# Power.net
KiCad netlist of a schematic drawn in Altium Designer
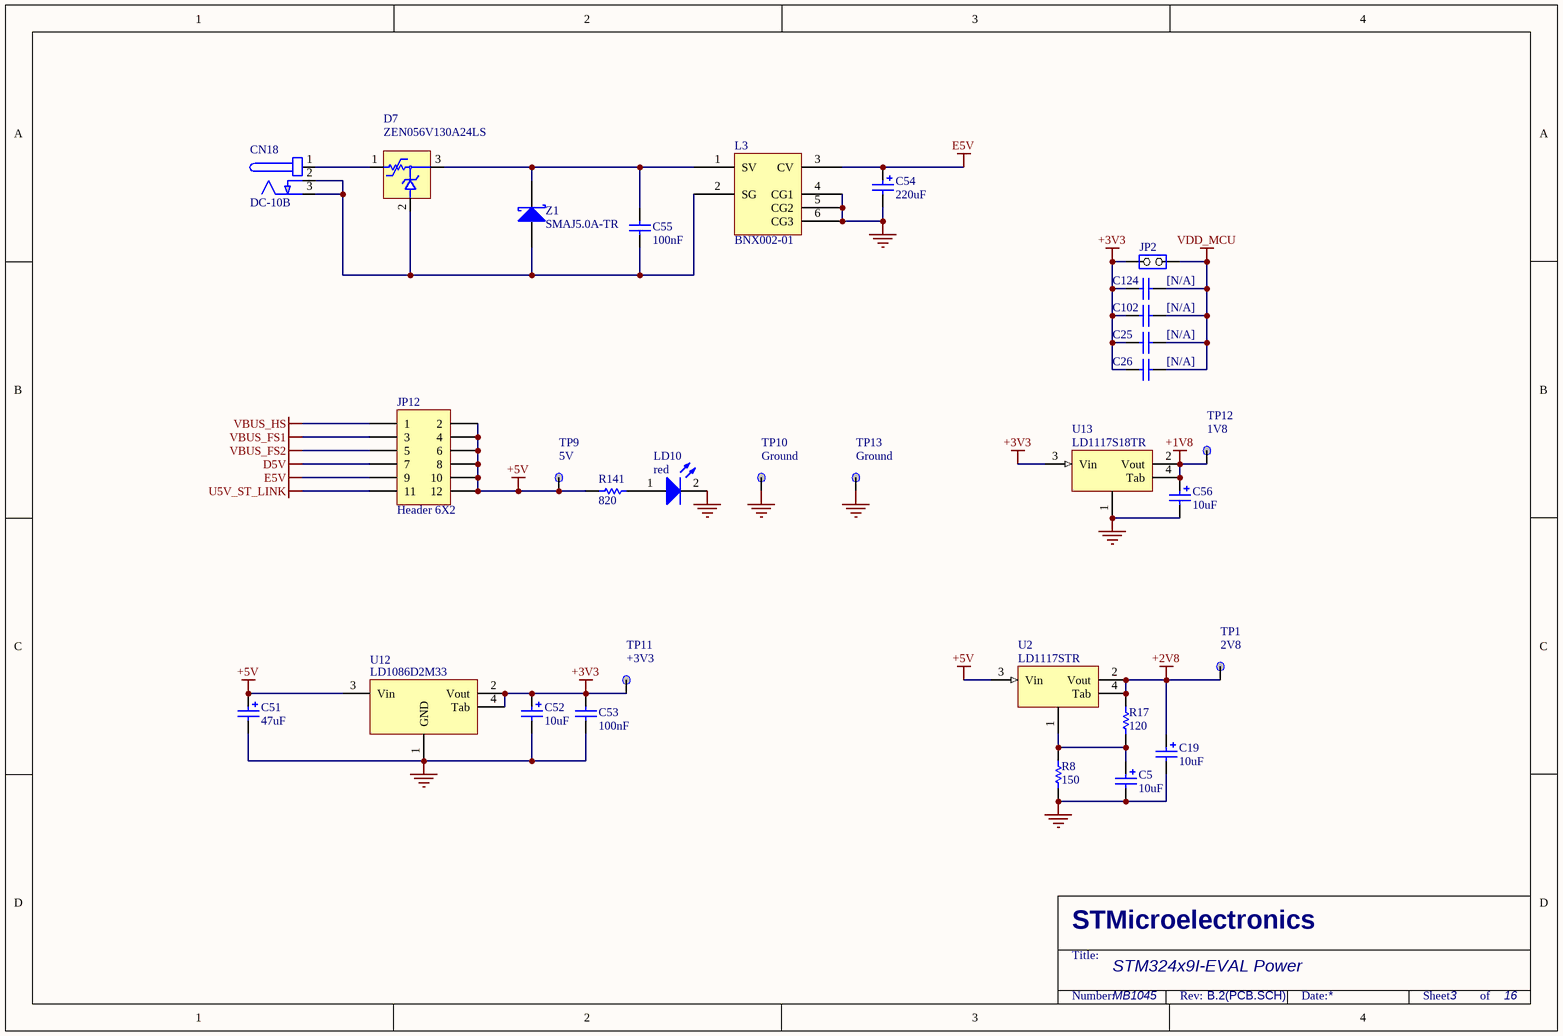
[diagram p0: Power.SchDoc]

(export (version "E")
  (design (tool "Eeschema 10.0.6"))
  (components
    (comp (ref "C5")
      (value "10uF")
      (footprint "TAN-A")
      (description "Polarized Capacitor (Radial)")
      (fields (field (name "PUBLISHER") "Altium Limited"))
      (libsource (lib "Miscellaneous Devices") (part "Cap Pol1"))
    )
    (comp (ref "C19")
      (value "10uF")
      (footprint "TAN-A")
      (description "Polarized Capacitor (Radial)")
      (fields (field (name "PUBLISHER") "Altium Limited"))
      (libsource (lib "Miscellaneous Devices") (part "Cap Pol1"))
    )
    (comp (ref "C25")
      (value "[N/A]")
      (footprint "0603C")
      (description "Capacitor")
      (fields (field (name "PUBLISHER") "Altium Limited"))
      (libsource (lib "Miscellaneous Devices") (part "Cap"))
    )
    (comp (ref "C26")
      (value "[N/A]")
      (footprint "0603C")
      (description "Capacitor")
      (fields (field (name "PUBLISHER") "Altium Limited"))
      (libsource (lib "Miscellaneous Devices") (part "Cap"))
    )
    (comp (ref "C51")
      (value "47uF")
      (footprint "CAE_5R3X5R3_H5R4")
      (description "Polarized Capacitor (Radial)")
      (fields (field (name "PUBLISHER") "Altium Limited"))
      (libsource (lib "Miscellaneous Devices") (part "Cap Pol1"))
    )
    (comp (ref "C52")
      (value "10uF")
      (footprint "TAN-A")
      (description "Polarized Capacitor (Radial)")
      (fields (field (name "PUBLISHER") "Altium Limited"))
      (libsource (lib "Miscellaneous Devices") (part "Cap Pol1"))
    )
    (comp (ref "C53")
      (value "100nF")
      (footprint "0603C")
      (description "Capacitor")
      (fields (field (name "PUBLISHER") "Altium Limited"))
      (libsource (lib "Miscellaneous Devices") (part "Cap"))
    )
    (comp (ref "C54")
      (value "220uF")
      (footprint "c310m-6")
      (description "Polarized Capacitor (Radial)")
      (fields (field (name "PUBLISHER") "Altium Limited"))
      (libsource (lib "Miscellaneous Devices") (part "Cap Pol1"))
    )
    (comp (ref "C55")
      (value "100nF")
      (footprint "0603C")
      (description "Capacitor")
      (fields (field (name "PUBLISHER") "Altium Limited"))
      (libsource (lib "Miscellaneous Devices") (part "CAP"))
    )
    (comp (ref "C56")
      (value "10uF")
      (footprint "TAN-A")
      (description "Polarized Capacitor (Radial)")
      (fields (field (name "PUBLISHER") "Altium Limited"))
      (libsource (lib "Miscellaneous Devices") (part "Cap Pol1"))
    )
    (comp (ref "C102")
      (value "[N/A]")
      (footprint "0603C")
      (description "Capacitor")
      (fields (field (name "PUBLISHER") "Altium Limited"))
      (libsource (lib "Miscellaneous Devices") (part "Cap"))
    )
    (comp (ref "C124")
      (value "[N/A]")
      (footprint "0603C")
      (description "Capacitor")
      (fields (field (name "PUBLISHER") "Altium Limited"))
      (libsource (lib "Miscellaneous Devices") (part "Cap"))
    )
    (comp (ref "CN18")
      (value "DC-10B")
      (footprint "PWR_JACK_DC10")
      (libsource (lib "STR910_SCHLIB") (part "PJ202A"))
    )
    (comp (ref "D7")
      (value "ZEN056V130A24LS")
      (footprint "TYCO_ZEN056V130A24LS")
      (libsource (lib "STR910_SCHLIB") (part "ZEN056V130A24LS"))
    )
    (comp (ref "JP2") (value "~") (footprint "SIP2") (libsource (lib "*") (part "JP2")))
    (comp (ref "JP12")
      (value "Header 6X2")
      (footprint "HDR_2X6_2R54")
      (description "Header, 6-Pin, Dual row")
      (fields (field (name "PUBLISHER") "Altium Limited"))
      (libsource (lib "mb1045") (part "Header 6X2"))
    )
    (comp (ref "L3")
      (value "BNX002-01")
      (footprint "BNX001")
      (libsource (lib "STR910_SCHLIB") (part "BNX002"))
    )
    (comp (ref "LD10")
      (value "red")
      (footprint "0603D")
      (description "Typical RED, GREEN, YELLOW, AMBER GaAs LED")
      (fields (field (name "PUBLISHER") "Altium Limited"))
      (libsource (lib "Miscellaneous Devices") (part "LED2"))
    )
    (comp (ref "R8")
      (value "150")
      (footprint "0603R")
      (description "Resistor")
      (fields (field (name "PUBLISHER") "Altium Limited"))
      (libsource (lib "Miscellaneous Devices") (part "res1"))
    )
    (comp (ref "R17")
      (value "120")
      (footprint "0603R")
      (description "Resistor")
      (fields (field (name "PUBLISHER") "Altium Limited"))
      (libsource (lib "Miscellaneous Devices") (part "res1"))
    )
    (comp (ref "R141")
      (value "820")
      (footprint "0603R")
      (description "Resistor")
      (fields (field (name "PUBLISHER") "Altium Limited"))
      (libsource (lib "Miscellaneous Devices") (part "res1"))
    )
    (comp (ref "TP1") (value "2V8") (footprint "TP") (libsource (lib "*") (part "TP")))
    (comp (ref "TP9") (value "5V") (footprint "TP") (libsource (lib "*") (part "TP")))
    (comp (ref "TP10") (value "Ground") (footprint "TP") (libsource (lib "*") (part "TP")))
    (comp (ref "TP11") (value "+3V3") (footprint "TP") (libsource (lib "*") (part "TP")))
    (comp (ref "TP12") (value "1V8") (footprint "TP") (libsource (lib "*") (part "TP")))
    (comp (ref "TP13") (value "Ground") (footprint "TP") (libsource (lib "*") (part "TP")))
    (comp (ref "U2") (value "LD1117STR") (footprint "SOT-223") (libsource (lib "mb1045") (part "LD1117")))
    (comp (ref "U12")
      (value "LD1086D2M33")
      (footprint "TO263-3")
      (libsource (lib "mb1045") (part "VOLTREG1"))
    )
    (comp (ref "U13") (value "LD1117S18TR") (footprint "SOT-223") (libsource (lib "mb1045") (part "LD1117")))
    (comp (ref "Z1")
      (value "SMAJ5.0A-TR")
      (footprint "sma")
      (description "Schottky Diode")
      (fields (field (name "PUBLISHER") "Altium Limited"))
      (libsource (lib "Miscellaneous Devices") (part "D Schottky"))
    )
  )
  (nets
    (net (code "1") (name "+1V8") (class "Default")
      (node (ref "C56") (pin "1") (pinfunction "1_1") (pintype "passive"))
      (node (ref "TP12") (pin "1") (pinfunction "1_1") (pintype "passive"))
      (node (ref "U13") (pin "2") (pinfunction "Vout_2") (pintype "power_in"))
      (node (ref "U13") (pin "4") (pinfunction "Tab_4") (pintype "power_in"))
    )
    (net (code "2") (name "+2V8") (class "Default")
      (node (ref "C19") (pin "1") (pinfunction "1_1") (pintype "passive"))
      (node (ref "R17") (pin "1") (pinfunction "1_1") (pintype "passive"))
      (node (ref "TP1") (pin "1") (pinfunction "1_1") (pintype "passive"))
      (node (ref "U2") (pin "2") (pinfunction "Vout_2") (pintype "power_in"))
      (node (ref "U2") (pin "4") (pinfunction "Tab_4") (pintype "power_in"))
    )
    (net (code "3") (name "+3V3") (class "Default")
      (node (ref "C102") (pin "1") (pinfunction "1_1") (pintype "passive"))
      (node (ref "C124") (pin "1") (pinfunction "1_1") (pintype "passive"))
      (node (ref "C25") (pin "1") (pinfunction "1_1") (pintype "passive"))
      (node (ref "C26") (pin "1") (pinfunction "1_1") (pintype "passive"))
      (node (ref "C52") (pin "1") (pinfunction "1_1") (pintype "passive"))
      (node (ref "C53") (pin "1") (pinfunction "1_1") (pintype "passive"))
      (node (ref "JP2") (pin "1") (pinfunction "COMMON_1") (pintype "passive"))
      (node (ref "TP11") (pin "1") (pinfunction "1_1") (pintype "passive"))
      (node (ref "U12") (pin "2") (pinfunction "Vout_2") (pintype "passive"))
      (node (ref "U12") (pin "4") (pinfunction "Tab_4") (pintype "passive"))
      (node (ref "U13") (pin "3") (pinfunction "Vin_3") (pintype "input"))
    )
    (net (code "4") (name "+5V") (class "Default")
      (node (ref "C51") (pin "1") (pinfunction "1_1") (pintype "passive"))
      (node (ref "JP12") (pin "10") (pinfunction "10_10") (pintype "passive"))
      (node (ref "JP12") (pin "12") (pinfunction "12_12") (pintype "passive"))
      (node (ref "JP12") (pin "2") (pinfunction "2_2") (pintype "passive"))
      (node (ref "JP12") (pin "4") (pinfunction "4_4") (pintype "passive"))
      (node (ref "JP12") (pin "6") (pinfunction "6_6") (pintype "passive"))
      (node (ref "JP12") (pin "8") (pinfunction "8_8") (pintype "passive"))
      (node (ref "R141") (pin "2") (pinfunction "2_2") (pintype "passive"))
      (node (ref "TP9") (pin "1") (pinfunction "1_1") (pintype "passive"))
      (node (ref "U12") (pin "3") (pinfunction "Vin_3") (pintype "passive"))
      (node (ref "U2") (pin "3") (pinfunction "Vin_3") (pintype "input"))
    )
    (net (code "5") (name "D5V") (class "Default")
      (node (ref "JP12") (pin "7") (pinfunction "7_7") (pintype "passive"))
    )
    (net (code "6") (name "E5V") (class "Default")
      (node (ref "C54") (pin "1") (pinfunction "1_1") (pintype "passive"))
      (node (ref "JP12") (pin "9") (pinfunction "9_9") (pintype "passive"))
      (node (ref "L3") (pin "3") (pinfunction "CV_3") (pintype "passive"))
    )
    (net (code "7") (name "GND") (class "Default")
      (node (ref "C19") (pin "2") (pinfunction "2_2") (pintype "passive"))
      (node (ref "C5") (pin "2") (pinfunction "2_2") (pintype "passive"))
      (node (ref "C51") (pin "2") (pinfunction "2_2") (pintype "passive"))
      (node (ref "C52") (pin "2") (pinfunction "2_2") (pintype "passive"))
      (node (ref "C53") (pin "2") (pinfunction "2_2") (pintype "passive"))
      (node (ref "C54") (pin "2") (pinfunction "2_2") (pintype "passive"))
      (node (ref "C56") (pin "2") (pinfunction "2_2") (pintype "passive"))
      (node (ref "L3") (pin "4") (pinfunction "CG1_4") (pintype "passive"))
      (node (ref "L3") (pin "5") (pinfunction "CG2_5") (pintype "passive"))
      (node (ref "L3") (pin "6") (pinfunction "CG3_6") (pintype "passive"))
      (node (ref "LD10") (pin "2") (pinfunction "K_2") (pintype "passive"))
      (node (ref "R8") (pin "2") (pinfunction "2_2") (pintype "passive"))
      (node (ref "TP10") (pin "1") (pinfunction "1_1") (pintype "passive"))
      (node (ref "TP13") (pin "1") (pinfunction "1_1") (pintype "passive"))
      (node (ref "U12") (pin "1") (pinfunction "GND_1") (pintype "passive"))
      (node (ref "U13") (pin "1") (pintype "passive"))
    )
    (net (code "8") (name "Net-(C5-Pad1)") (class "Default")
      (node (ref "C5") (pin "1") (pinfunction "1_1") (pintype "passive"))
      (node (ref "R17") (pin "2") (pinfunction "2_2") (pintype "passive"))
      (node (ref "R8") (pin "1") (pinfunction "1_1") (pintype "passive"))
      (node (ref "U2") (pin "1") (pintype "passive"))
    )
    (net (code "9") (name "Net-(CN18-+)") (class "Default")
      (node (ref "CN18") (pin "1") (pinfunction "+_1") (pintype "passive"))
      (node (ref "D7") (pin "1") (pintype "passive"))
    )
    (net (code "10") (name "Net-(L3-SG)") (class "Default")
      (node (ref "C55") (pin "2") (pinfunction "2_2") (pintype "passive"))
      (node (ref "CN18") (pin "2") (pinfunction "GND_2") (pintype "passive"))
      (node (ref "CN18") (pin "3") (pinfunction "GND_3") (pintype "passive"))
      (node (ref "D7") (pin "2") (pintype "passive"))
      (node (ref "L3") (pin "2") (pinfunction "SG_2") (pintype "passive"))
      (node (ref "Z1") (pin "1") (pinfunction "A_1") (pintype "passive"))
    )
    (net (code "11") (name "Net-(L3-SV)") (class "Default")
      (node (ref "C55") (pin "1") (pinfunction "1_1") (pintype "passive"))
      (node (ref "D7") (pin "3") (pintype "passive"))
      (node (ref "L3") (pin "1") (pinfunction "SV_1") (pintype "passive"))
      (node (ref "Z1") (pin "2") (pinfunction "K_2") (pintype "passive"))
    )
    (net (code "12") (name "Net-(LD10-A)") (class "Default")
      (node (ref "LD10") (pin "1") (pinfunction "A_1") (pintype "passive"))
      (node (ref "R141") (pin "1") (pinfunction "1_1") (pintype "passive"))
    )
    (net (code "13") (name "U5V_ST_LINK") (class "Default")
      (node (ref "JP12") (pin "11") (pinfunction "11_11") (pintype "passive"))
    )
    (net (code "14") (name "VBUS_FS1") (class "Default")
      (node (ref "JP12") (pin "3") (pinfunction "3_3") (pintype "passive"))
    )
    (net (code "15") (name "VBUS_FS2") (class "Default")
      (node (ref "JP12") (pin "5") (pinfunction "5_5") (pintype "passive"))
    )
    (net (code "16") (name "VBUS_HS") (class "Default")
      (node (ref "JP12") (pin "1") (pinfunction "1_1") (pintype "passive"))
    )
    (net (code "17") (name "VDD_MCU") (class "Default")
      (node (ref "C102") (pin "2") (pinfunction "2_2") (pintype "passive"))
      (node (ref "C124") (pin "2") (pinfunction "2_2") (pintype "passive"))
      (node (ref "C25") (pin "2") (pinfunction "2_2") (pintype "passive"))
      (node (ref "C26") (pin "2") (pinfunction "2_2") (pintype "passive"))
      (node (ref "JP2") (pin "2") (pinfunction "NO_2") (pintype "passive"))
    )
  )
)
